# Pin_Connections.net
KiCad netlist of a schematic drawn in Altium Designer
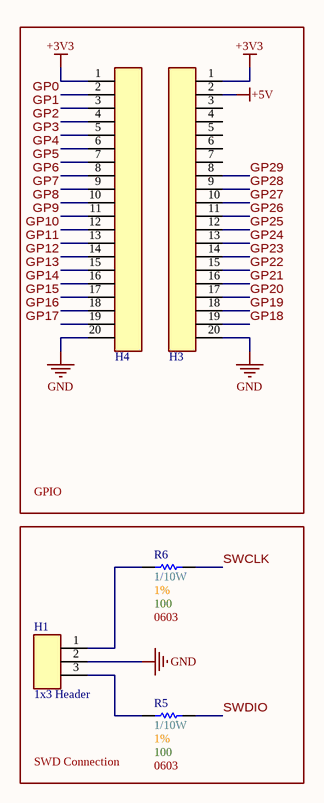
[diagram p0: Pin Connections.SchDoc]

(export (version "E")
  (design (tool "Eeschema 10.0.6"))
  (components
    (comp (ref "H1")
      (value "1x3 Header")
      (footprint "[Header] 1x3 Male")
      (description "2.54mm pitch")
      (libsource (lib "Connectors") (part "[Header] 1x3 Male"))
    )
    (comp (ref "H3")
      (value "1x20 Header")
      (footprint "[Header] 1x20 Male")
      (description "2.54mm pitch")
      (libsource (lib "Connectors") (part "[Header] 1x20 Male"))
    )
    (comp (ref "H4")
      (value "1x20 Header")
      (footprint "[Header] 1x20 Male")
      (description "2.54mm pitch")
      (libsource (lib "") (part "[Header] 1x20 Male_1"))
    )
    (comp (ref "R5")
      (value "[100] SMD 0603 1% 1/10W")
      (footprint "[Res] SMD 0603")
      (description "RC0603FR-07100RL")
      (fields
        (field (name "WATTAGE") "1/10W")
        (field (name "TOLERANCE") "1%")
        (field (name "RESISTANCE") "100")
        (field (name "SIZE PACKAGE") "0603")
      )
      (libsource (lib "Resistors") (part "[100] SMD 0603 1% 1/10W"))
    )
    (comp (ref "R6")
      (value "[100] SMD 0603 1% 1/10W")
      (footprint "[Res] SMD 0603")
      (description "RC0603FR-07100RL")
      (fields
        (field (name "WATTAGE") "1/10W")
        (field (name "TOLERANCE") "1%")
        (field (name "RESISTANCE") "100")
        (field (name "SIZE PACKAGE") "0603")
      )
      (libsource (lib "Resistors") (part "[100] SMD 0603 1% 1/10W"))
    )
  )
  (nets
    (net (code "1") (name "+3V3") (class "Default")
      (node (ref "H3") (pin "1") (pinfunction "1_1") (pintype "passive"))
      (node (ref "H4") (pin "1") (pinfunction "1_1") (pintype "passive"))
    )
    (net (code "2") (name "+5V") (class "Default")
      (node (ref "H3") (pin "2") (pinfunction "2_2") (pintype "passive"))
    )
    (net (code "3") (name "/GP0") (class "Default")
      (node (ref "H4") (pin "2") (pinfunction "2_2") (pintype "passive"))
    )
    (net (code "4") (name "/GP1") (class "Default")
      (node (ref "H4") (pin "3") (pinfunction "3_3") (pintype "passive"))
    )
    (net (code "5") (name "/GP2") (class "Default")
      (node (ref "H4") (pin "4") (pinfunction "4_4") (pintype "passive"))
    )
    (net (code "6") (name "/GP3") (class "Default")
      (node (ref "H4") (pin "5") (pinfunction "5_5") (pintype "passive"))
    )
    (net (code "7") (name "/GP4") (class "Default")
      (node (ref "H4") (pin "6") (pinfunction "6_6") (pintype "passive"))
    )
    (net (code "8") (name "/GP5") (class "Default")
      (node (ref "H4") (pin "7") (pinfunction "7_7") (pintype "passive"))
    )
    (net (code "9") (name "/GP6") (class "Default")
      (node (ref "H4") (pin "8") (pinfunction "8_8") (pintype "passive"))
    )
    (net (code "10") (name "/GP7") (class "Default")
      (node (ref "H4") (pin "9") (pinfunction "9_9") (pintype "passive"))
    )
    (net (code "11") (name "/GP8") (class "Default")
      (node (ref "H4") (pin "10") (pinfunction "10_10") (pintype "passive"))
    )
    (net (code "12") (name "/GP9") (class "Default")
      (node (ref "H4") (pin "11") (pinfunction "1_11") (pintype "passive"))
    )
    (net (code "13") (name "/GP10") (class "Default")
      (node (ref "H4") (pin "12") (pinfunction "2_12") (pintype "passive"))
    )
    (net (code "14") (name "/GP11") (class "Default")
      (node (ref "H4") (pin "13") (pinfunction "3_13") (pintype "passive"))
    )
    (net (code "15") (name "/GP12") (class "Default")
      (node (ref "H4") (pin "14") (pinfunction "4_14") (pintype "passive"))
    )
    (net (code "16") (name "/GP13") (class "Default")
      (node (ref "H4") (pin "15") (pinfunction "5_15") (pintype "passive"))
    )
    (net (code "17") (name "/GP14") (class "Default")
      (node (ref "H4") (pin "16") (pinfunction "6_16") (pintype "passive"))
    )
    (net (code "18") (name "/GP15") (class "Default")
      (node (ref "H4") (pin "17") (pinfunction "7_17") (pintype "passive"))
    )
    (net (code "19") (name "/GP16") (class "Default")
      (node (ref "H4") (pin "18") (pinfunction "8_18") (pintype "passive"))
    )
    (net (code "20") (name "/GP17") (class "Default")
      (node (ref "H4") (pin "19") (pinfunction "9_19") (pintype "passive"))
    )
    (net (code "21") (name "/GP18") (class "Default")
      (node (ref "H3") (pin "19") (pinfunction "9_19") (pintype "passive"))
    )
    (net (code "22") (name "/GP19") (class "Default")
      (node (ref "H3") (pin "18") (pinfunction "8_18") (pintype "passive"))
    )
    (net (code "23") (name "/GP20") (class "Default")
      (node (ref "H3") (pin "17") (pinfunction "7_17") (pintype "passive"))
    )
    (net (code "24") (name "/GP21") (class "Default")
      (node (ref "H3") (pin "16") (pinfunction "6_16") (pintype "passive"))
    )
    (net (code "25") (name "/GP22") (class "Default")
      (node (ref "H3") (pin "15") (pinfunction "5_15") (pintype "passive"))
    )
    (net (code "26") (name "/GP23") (class "Default")
      (node (ref "H3") (pin "14") (pinfunction "4_14") (pintype "passive"))
    )
    (net (code "27") (name "/GP24") (class "Default")
      (node (ref "H3") (pin "13") (pinfunction "3_13") (pintype "passive"))
    )
    (net (code "28") (name "/GP25") (class "Default")
      (node (ref "H3") (pin "12") (pinfunction "2_12") (pintype "passive"))
    )
    (net (code "29") (name "/GP26") (class "Default")
      (node (ref "H3") (pin "11") (pinfunction "1_11") (pintype "passive"))
    )
    (net (code "30") (name "/GP27") (class "Default")
      (node (ref "H3") (pin "10") (pinfunction "10_10") (pintype "passive"))
    )
    (net (code "31") (name "/GP28") (class "Default")
      (node (ref "H3") (pin "9") (pinfunction "9_9") (pintype "passive"))
    )
    (net (code "32") (name "/GP29") (class "Default")
      (node (ref "H3") (pin "8") (pinfunction "8_8") (pintype "passive"))
    )
    (net (code "33") (name "/SWCLK") (class "Default")
      (node (ref "R6") (pin "2") (pinfunction "2_2") (pintype "passive"))
    )
    (net (code "34") (name "/SWDIO") (class "Default")
      (node (ref "R5") (pin "2") (pinfunction "2_2") (pintype "passive"))
    )
    (net (code "35") (name "GND") (class "Default")
      (node (ref "H1") (pin "2") (pintype "passive"))
      (node (ref "H3") (pin "20") (pinfunction "10_20") (pintype "passive"))
      (node (ref "H4") (pin "20") (pinfunction "10_20") (pintype "passive"))
    )
    (net (code "36") (name "Net-(H1-Pad1)") (class "Default")
      (node (ref "H1") (pin "1") (pintype "passive"))
      (node (ref "R6") (pin "1") (pinfunction "1_1") (pintype "passive"))
    )
    (net (code "37") (name "Net-(H1-Pad3)") (class "Default")
      (node (ref "H1") (pin "3") (pintype "passive"))
      (node (ref "R5") (pin "1") (pinfunction "1_1") (pintype "passive"))
    )
    (net (code "38") (name "unconnected-(H3-Pad3)") (class "Default")
      (node (ref "H3") (pin "3") (pinfunction "3_3") (pintype "passive"))
    )
    (net (code "39") (name "unconnected-(H3-Pad4)") (class "Default")
      (node (ref "H3") (pin "4") (pinfunction "4_4") (pintype "passive"))
    )
    (net (code "40") (name "unconnected-(H3-Pad5)") (class "Default")
      (node (ref "H3") (pin "5") (pinfunction "5_5") (pintype "passive"))
    )
    (net (code "41") (name "unconnected-(H3-Pad6)") (class "Default")
      (node (ref "H3") (pin "6") (pinfunction "6_6") (pintype "passive"))
    )
    (net (code "42") (name "unconnected-(H3-Pad7)") (class "Default")
      (node (ref "H3") (pin "7") (pinfunction "7_7") (pintype "passive"))
    )
  )
)
